# Haptic_Drivers.net
KiCad netlist of a schematic drawn in Altium Designer
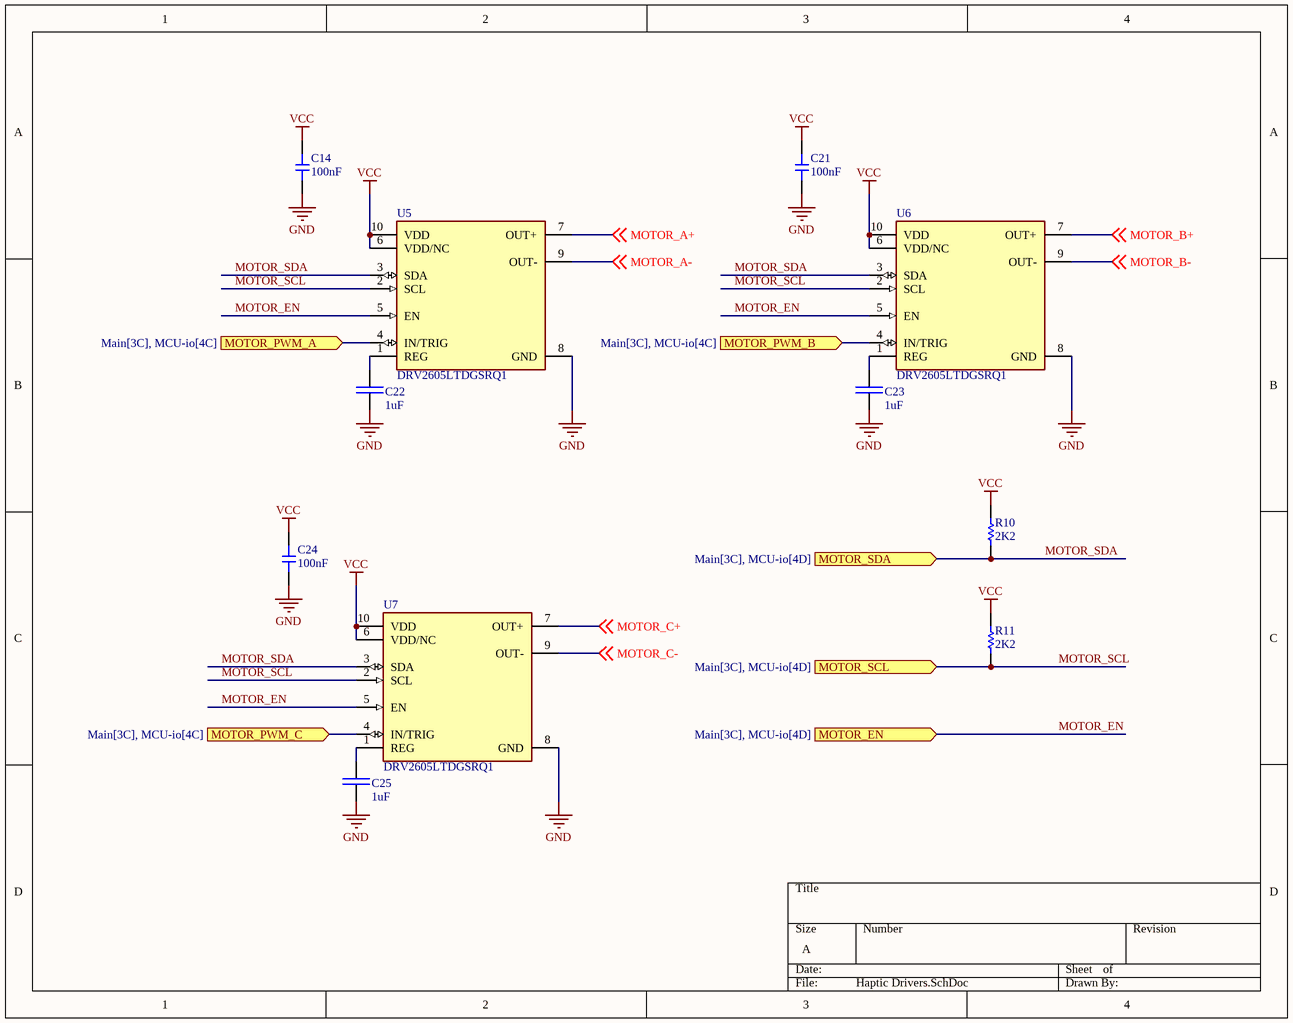
[diagram p0: Haptic Drivers.SchDoc]

(export (version "E")
  (design (tool "Eeschema 10.0.6"))
  (components
    (comp (ref "C14")
      (value "CC0603KRX7R9BB104")
      (footprint "CAP-0603")
      (description "Capacitor, Ceramic (MLCC), 100nF, ±10%, 50V, X7R, ±10%, SMD 0603")
      (fields
        (field (name "JLCPCB BASIC PART") "Yes")
        (field (name "CAPACITANCE") "100nF")
        (field (name "JLCPCB PART NUMBER") "C14663")
      )
      (libsource (lib "JLCCapacitor") (part "CC0603KRX7R9BB104"))
    )
    (comp (ref "C21")
      (value "CC0603KRX7R9BB104")
      (footprint "CAP-0603")
      (description "Capacitor, Ceramic (MLCC), 100nF, ±10%, 50V, X7R, ±10%, SMD 0603")
      (fields
        (field (name "JLCPCB BASIC PART") "Yes")
        (field (name "CAPACITANCE") "100nF")
        (field (name "JLCPCB PART NUMBER") "C14663")
      )
      (libsource (lib "JLCCapacitor") (part "CC0603KRX7R9BB104"))
    )
    (comp (ref "C22")
      (value "1uF")
      (footprint "CAP_SM0603_YAGEOCC2_N")
      (description "CAP 1uF SM0603 X7R 50V YAGEO CC2")
      (fields
        (field (name "MANUFACTURER") "Yageo")
        (field (name "MANUFACTURER PART NUMBER") "CC0603KRX7R9BB183")
      )
      (libsource (lib "ResistorCapsInductors") (part "CC0603KRX7R9BB105"))
    )
    (comp (ref "C23")
      (value "1uF")
      (footprint "CAP_SM0603_YAGEOCC2_N")
      (description "CAP 1uF SM0603 X7R 50V YAGEO CC2")
      (fields
        (field (name "MANUFACTURER") "Yageo")
        (field (name "MANUFACTURER PART NUMBER") "CC0603KRX7R9BB183")
      )
      (libsource (lib "ResistorCapsInductors") (part "CC0603KRX7R9BB105"))
    )
    (comp (ref "C24")
      (value "CC0603KRX7R9BB104")
      (footprint "CAP-0603")
      (description "Capacitor, Ceramic (MLCC), 100nF, ±10%, 50V, X7R, ±10%, SMD 0603")
      (fields
        (field (name "JLCPCB BASIC PART") "Yes")
        (field (name "CAPACITANCE") "100nF")
        (field (name "JLCPCB PART NUMBER") "C14663")
      )
      (libsource (lib "JLCCapacitor") (part "CC0603KRX7R9BB104"))
    )
    (comp (ref "C25")
      (value "1uF")
      (footprint "CAP_SM0603_YAGEOCC2_N")
      (description "CAP 1uF SM0603 X7R 50V YAGEO CC2")
      (fields
        (field (name "MANUFACTURER") "Yageo")
        (field (name "MANUFACTURER PART NUMBER") "CC0603KRX7R9BB183")
      )
      (libsource (lib "ResistorCapsInductors") (part "CC0603KRX7R9BB105"))
    )
    (comp (ref "R10")
      (value "2K2")
      (footprint "RES_SM0603_YAGEORC_N")
      (description "RES 2K2 SM0603 YAGEO RC_L")
      (fields
        (field (name "MANUFACTURER") "Yageo")
        (field (name "MANUFACTURER PART NUMBER") "RC0603FR-072K2L")
      )
      (libsource (lib "ResistorCapsInductors") (part "RC0603FR-072K2L"))
    )
    (comp (ref "R11")
      (value "2K2")
      (footprint "RES_SM0603_YAGEORC_N")
      (description "RES 2K2 SM0603 YAGEO RC_L")
      (fields
        (field (name "MANUFACTURER") "Yageo")
        (field (name "MANUFACTURER PART NUMBER") "RC0603FR-072K2L")
      )
      (libsource (lib "ResistorCapsInductors") (part "RC0603FR-072K2L"))
    )
    (comp (ref "U5")
      (value "DRV2605LTDGSRQ1")
      (footprint "FP-DGS0010A-IPC_B")
      (description "IC MOTOR DRIVER 2V-5.2V 10VSSOP")
      (libsource (lib "Altium Content Vault") (part "d35f95fce1212857174f9b556b1b73d"))
    )
    (comp (ref "U6")
      (value "DRV2605LTDGSRQ1")
      (footprint "FP-DGS0010A-IPC_B")
      (description "IC MOTOR DRIVER 2V-5.2V 10VSSOP")
      (libsource (lib "Altium Content Vault") (part "d35f95fce1212857174f9b556b1b73d"))
    )
    (comp (ref "U7")
      (value "DRV2605LTDGSRQ1")
      (footprint "FP-DGS0010A-IPC_B")
      (description "IC MOTOR DRIVER 2V-5.2V 10VSSOP")
      (libsource (lib "Altium Content Vault") (part "d35f95fce1212857174f9b556b1b73d"))
    )
  )
  (nets
    (net (code "1") (name "/MOTOR_EN") (class "Default")
      (node (ref "U5") (pin "5") (pinfunction "EN_5") (pintype "input"))
      (node (ref "U6") (pin "5") (pinfunction "EN_5") (pintype "input"))
      (node (ref "U7") (pin "5") (pinfunction "EN_5") (pintype "input"))
    )
    (net (code "2") (name "/MOTOR_PWM_A") (class "Default")
      (node (ref "U5") (pin "4") (pinfunction "IN/TRIG_4") (pintype "bidirectional"))
    )
    (net (code "3") (name "/MOTOR_PWM_B") (class "Default")
      (node (ref "U6") (pin "4") (pinfunction "IN/TRIG_4") (pintype "bidirectional"))
    )
    (net (code "4") (name "/MOTOR_PWM_C") (class "Default")
      (node (ref "U7") (pin "4") (pinfunction "IN/TRIG_4") (pintype "bidirectional"))
    )
    (net (code "5") (name "/MOTOR_SCL") (class "Default")
      (node (ref "R11") (pin "1") (pinfunction "1_1") (pintype "passive"))
      (node (ref "U5") (pin "2") (pinfunction "SCL_2") (pintype "input"))
      (node (ref "U6") (pin "2") (pinfunction "SCL_2") (pintype "input"))
      (node (ref "U7") (pin "2") (pinfunction "SCL_2") (pintype "input"))
    )
    (net (code "6") (name "/MOTOR_SDA") (class "Default")
      (node (ref "R10") (pin "1") (pinfunction "1_1") (pintype "passive"))
      (node (ref "U5") (pin "3") (pinfunction "SDA_3") (pintype "bidirectional"))
      (node (ref "U6") (pin "3") (pinfunction "SDA_3") (pintype "bidirectional"))
      (node (ref "U7") (pin "3") (pinfunction "SDA_3") (pintype "bidirectional"))
    )
    (net (code "7") (name "GND") (class "Default")
      (node (ref "C14") (pin "1") (pinfunction "1_1") (pintype "passive"))
      (node (ref "C21") (pin "1") (pinfunction "1_1") (pintype "passive"))
      (node (ref "C22") (pin "2") (pintype "passive"))
      (node (ref "C23") (pin "2") (pintype "passive"))
      (node (ref "C24") (pin "1") (pinfunction "1_1") (pintype "passive"))
      (node (ref "C25") (pin "2") (pintype "passive"))
      (node (ref "U5") (pin "8") (pinfunction "GND_8") (pintype "power_in"))
      (node (ref "U6") (pin "8") (pinfunction "GND_8") (pintype "power_in"))
      (node (ref "U7") (pin "8") (pinfunction "GND_8") (pintype "power_in"))
    )
    (net (code "8") (name "MOTOR_A+") (class "Default")
      (node (ref "U5") (pin "7") (pinfunction "OUT+_7") (pintype "passive"))
    )
    (net (code "9") (name "MOTOR_A-") (class "Default")
      (node (ref "U5") (pin "9") (pinfunction "OUT-_9") (pintype "passive"))
    )
    (net (code "10") (name "MOTOR_B+") (class "Default")
      (node (ref "U6") (pin "7") (pinfunction "OUT+_7") (pintype "passive"))
    )
    (net (code "11") (name "MOTOR_B-") (class "Default")
      (node (ref "U6") (pin "9") (pinfunction "OUT-_9") (pintype "passive"))
    )
    (net (code "12") (name "MOTOR_C+") (class "Default")
      (node (ref "U7") (pin "7") (pinfunction "OUT+_7") (pintype "passive"))
    )
    (net (code "13") (name "MOTOR_C-") (class "Default")
      (node (ref "U7") (pin "9") (pinfunction "OUT-_9") (pintype "passive"))
    )
    (net (code "14") (name "Net-(U5-REG)") (class "Default")
      (node (ref "C22") (pin "1") (pintype "passive"))
      (node (ref "U5") (pin "1") (pinfunction "REG_1") (pintype "passive"))
    )
    (net (code "15") (name "Net-(U6-REG)") (class "Default")
      (node (ref "C23") (pin "1") (pintype "passive"))
      (node (ref "U6") (pin "1") (pinfunction "REG_1") (pintype "passive"))
    )
    (net (code "16") (name "Net-(U7-REG)") (class "Default")
      (node (ref "C25") (pin "1") (pintype "passive"))
      (node (ref "U7") (pin "1") (pinfunction "REG_1") (pintype "passive"))
    )
    (net (code "17") (name "VCC") (class "Default")
      (node (ref "C14") (pin "2") (pinfunction "2_2") (pintype "passive"))
      (node (ref "C21") (pin "2") (pinfunction "2_2") (pintype "passive"))
      (node (ref "C24") (pin "2") (pinfunction "2_2") (pintype "passive"))
      (node (ref "R10") (pin "2") (pinfunction "2_2") (pintype "passive"))
      (node (ref "R11") (pin "2") (pinfunction "2_2") (pintype "passive"))
      (node (ref "U5") (pin "10") (pinfunction "VDD_10") (pintype "power_in"))
      (node (ref "U5") (pin "6") (pinfunction "VDD/NC_6") (pintype "power_in"))
      (node (ref "U6") (pin "10") (pinfunction "VDD_10") (pintype "power_in"))
      (node (ref "U6") (pin "6") (pinfunction "VDD/NC_6") (pintype "power_in"))
      (node (ref "U7") (pin "10") (pinfunction "VDD_10") (pintype "power_in"))
      (node (ref "U7") (pin "6") (pinfunction "VDD/NC_6") (pintype "power_in"))
    )
  )
)
